# UWB.net
KiCad netlist of a schematic drawn in Altium Designer
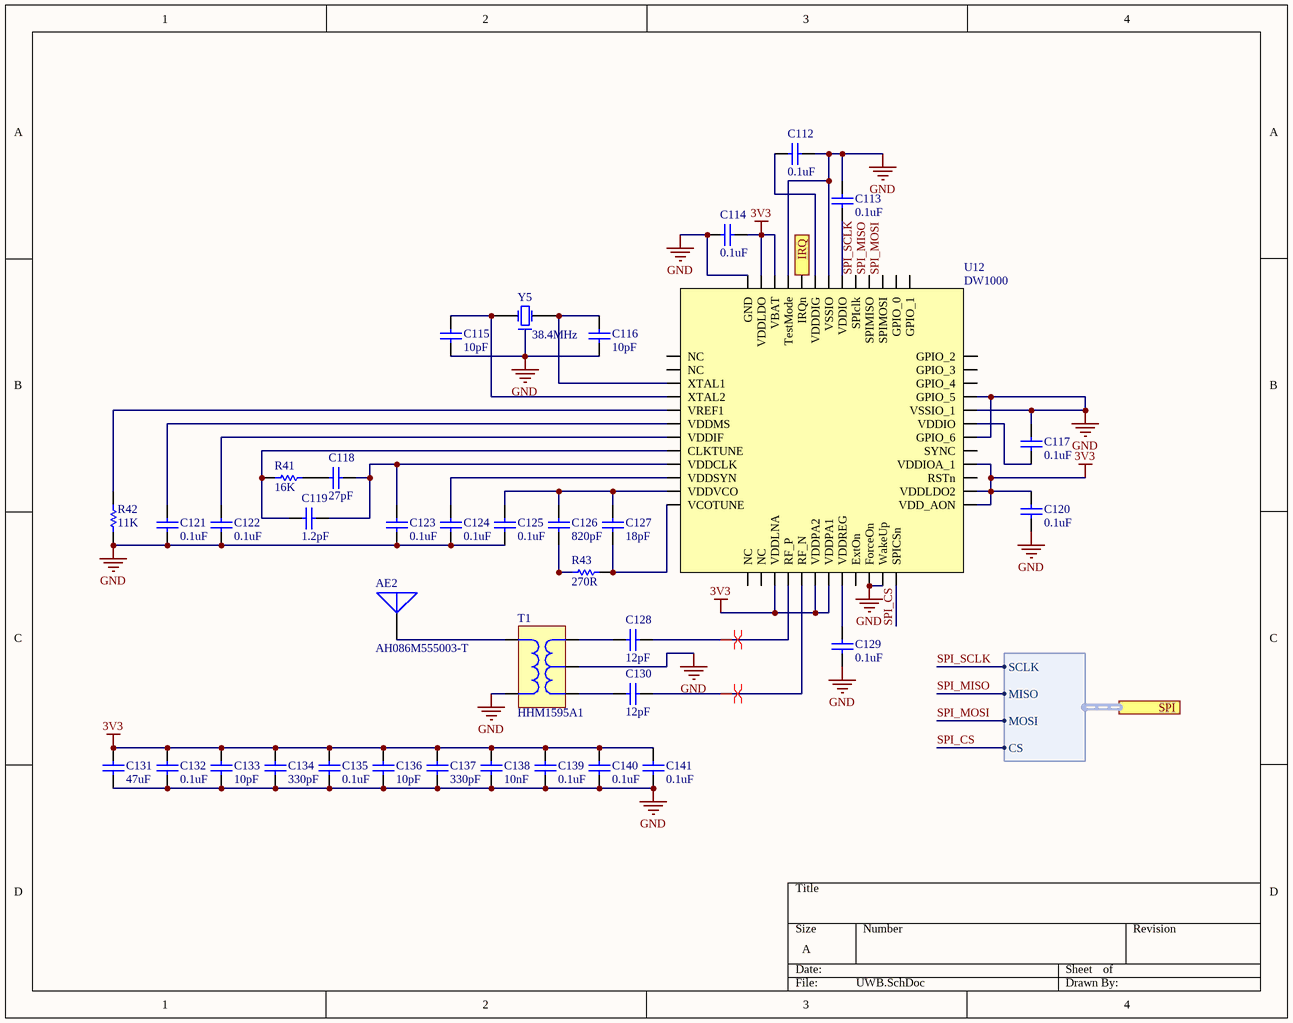
[diagram p0: UWB.SchDoc]

(export (version "E")
  (design (tool "Eeschema 10.0.6"))
  (components
    (comp (ref "AE2")
      (value "AH086M555003-T")
      (footprint "AH086M555003-T")
      (fields (field (name "MANUFACTURER") "Taiyo Yuden"))
      (libsource (lib "Components") (part "AH086M555003-T"))
    )
    (comp (ref "C112")
      (value "0.1uF")
      (footprint "C0402[1005X55]")
      (description "0.1uF 6.3V 10% 0402 (1005 Metric)")
      (fields (field (name "PARTNUMBER") "GRM155R70J104KA01D") (field (name "MANUFACTURER") "Murata"))
      (libsource (lib "Capacitors") (part "CAP_0.1uF_6.3V_0402_10%"))
    )
    (comp (ref "C113")
      (value "0.1uF")
      (footprint "C0402[1005X55]")
      (description "0.1uF 6.3V 10% 0402 (1005 Metric)")
      (fields (field (name "PARTNUMBER") "GRM155R70J104KA01D") (field (name "MANUFACTURER") "Murata"))
      (libsource (lib "Capacitors") (part "CAP_0.1uF_6.3V_0402_10%"))
    )
    (comp (ref "C114")
      (value "0.1uF")
      (footprint "C0402[1005X55]")
      (description "0.1uF 6.3V 10% 0402 (1005 Metric)")
      (fields (field (name "PARTNUMBER") "GRM155R70J104KA01D") (field (name "MANUFACTURER") "Murata"))
      (libsource (lib "Capacitors") (part "CAP_0.1uF_6.3V_0402_10%"))
    )
    (comp (ref "C115")
      (value "10pF")
      (footprint "C0402[1005X55]")
      (description "10pF 50V 1% 0402 (1005 Metric)")
      (fields (field (name "PARTNUMBER") "GRM1555C1H100FA01D") (field (name "MANUFACTURER") "Murata"))
      (libsource (lib "Capacitors") (part "CAP_10pF_50V_0402_1%"))
    )
    (comp (ref "C116")
      (value "10pF")
      (footprint "C0402[1005X55]")
      (description "10pF 50V 1% 0402 (1005 Metric)")
      (fields (field (name "PARTNUMBER") "GRM1555C1H100FA01D") (field (name "MANUFACTURER") "Murata"))
      (libsource (lib "Capacitors") (part "CAP_10pF_50V_0402_1%"))
    )
    (comp (ref "C117")
      (value "0.1uF")
      (footprint "C0402[1005X55]")
      (description "0.1uF 6.3V 10% 0402 (1005 Metric)")
      (fields (field (name "PARTNUMBER") "GRM155R70J104KA01D") (field (name "MANUFACTURER") "Murata"))
      (libsource (lib "Capacitors") (part "CAP_0.1uF_6.3V_0402_10%"))
    )
    (comp (ref "C118")
      (value "27pF")
      (footprint "C0402[1005X55]")
      (description "27pF 50V 1% 0402 (1005 Metric)")
      (fields (field (name "PARTNUMBER") "GRM1555C1H270FA01D") (field (name "MANUFACTURER") "Murata"))
      (libsource (lib "Capacitors") (part "CAP_27pF_50V_0402_1%"))
    )
    (comp (ref "C119")
      (value "1.2pF")
      (footprint "C0402[1005X55]")
      (description "1.2pF 50V 0.05pF 0402 (1005 Metric)")
      (fields (field (name "PARTNUMBER") "GRM1555C1H1R2WA01D") (field (name "MANUFACTURER") "Murata"))
      (libsource (lib "Capacitors") (part "CAP_1.2pF_50V_0402_0.05pF"))
    )
    (comp (ref "C120")
      (value "0.1uF")
      (footprint "C0402[1005X55]")
      (description "0.1uF 6.3V 10% 0402 (1005 Metric)")
      (fields (field (name "PARTNUMBER") "GRM155R70J104KA01D") (field (name "MANUFACTURER") "Murata"))
      (libsource (lib "Capacitors") (part "CAP_0.1uF_6.3V_0402_10%"))
    )
    (comp (ref "C121")
      (value "0.1uF")
      (footprint "C0402[1005X55]")
      (description "0.1uF 6.3V 10% 0402 (1005 Metric)")
      (fields (field (name "PARTNUMBER") "GRM155R70J104KA01D") (field (name "MANUFACTURER") "Murata"))
      (libsource (lib "Capacitors") (part "CAP_0.1uF_6.3V_0402_10%"))
    )
    (comp (ref "C122")
      (value "0.1uF")
      (footprint "C0402[1005X55]")
      (description "0.1uF 6.3V 10% 0402 (1005 Metric)")
      (fields (field (name "PARTNUMBER") "GRM155R70J104KA01D") (field (name "MANUFACTURER") "Murata"))
      (libsource (lib "Capacitors") (part "CAP_0.1uF_6.3V_0402_10%"))
    )
    (comp (ref "C123")
      (value "0.1uF")
      (footprint "C0402[1005X55]")
      (description "0.1uF 6.3V 10% 0402 (1005 Metric)")
      (fields (field (name "PARTNUMBER") "GRM155R70J104KA01D") (field (name "MANUFACTURER") "Murata"))
      (libsource (lib "Capacitors") (part "CAP_0.1uF_6.3V_0402_10%"))
    )
    (comp (ref "C124")
      (value "0.1uF")
      (footprint "C0402[1005X55]")
      (description "0.1uF 6.3V 10% 0402 (1005 Metric)")
      (fields (field (name "PARTNUMBER") "GRM155R70J104KA01D") (field (name "MANUFACTURER") "Murata"))
      (libsource (lib "Capacitors") (part "CAP_0.1uF_6.3V_0402_10%"))
    )
    (comp (ref "C125")
      (value "0.1uF")
      (footprint "C0402[1005X55]")
      (description "0.1uF 6.3V 10% 0402 (1005 Metric)")
      (fields (field (name "PARTNUMBER") "GRM155R70J104KA01D") (field (name "MANUFACTURER") "Murata"))
      (libsource (lib "Capacitors") (part "CAP_0.1uF_6.3V_0402_10%"))
    )
    (comp (ref "C126")
      (value "820pF")
      (footprint "C0402[1005X55]")
      (description "820pF 50V 5% 0402 (1005 Metric)")
      (fields (field (name "PARTNUMBER") "GRM1555C1H821JA01D") (field (name "MANUFACTURER") "Murata"))
      (libsource (lib "Capacitors") (part "CAP_820pF_50V_0402_5%"))
    )
    (comp (ref "C127")
      (value "18pF")
      (footprint "C0402[1005X55]")
      (description "18pF 50V 1% 0402 (1005 Metric)")
      (fields (field (name "PARTNUMBER") "GRM1555C1H180FA01D") (field (name "MANUFACTURER") "Murata"))
      (libsource (lib "Capacitors") (part "CAP_18pF_50V_0402_1%"))
    )
    (comp (ref "C128")
      (value "12pF")
      (footprint "C0402[1005X55]")
      (description "12pF 50V 5% 0402 (1005 Metric)")
      (fields (field (name "PARTNUMBER") "GRM1555C1H120JA01D") (field (name "MANUFACTURER") "Murata"))
      (libsource (lib "Capacitors") (part "CAP_12pF_50V_0402_5%"))
    )
    (comp (ref "C129")
      (value "0.1uF")
      (footprint "C0402[1005X55]")
      (description "0.1uF 6.3V 10% 0402 (1005 Metric)")
      (fields (field (name "PARTNUMBER") "GRM155R70J104KA01D") (field (name "MANUFACTURER") "Murata"))
      (libsource (lib "Capacitors") (part "CAP_0.1uF_6.3V_0402_10%"))
    )
    (comp (ref "C130")
      (value "12pF")
      (footprint "C0402[1005X55]")
      (description "12pF 50V 5% 0402 (1005 Metric)")
      (fields (field (name "PARTNUMBER") "GRM1555C1H120JA01D") (field (name "MANUFACTURER") "Murata"))
      (libsource (lib "Capacitors") (part "CAP_12pF_50V_0402_5%"))
    )
    (comp (ref "C131")
      (value "47uF")
      (footprint "C1206[3216X160]")
      (description "47uF 6.3V 10% 1206 (3216 Metric)")
      (fields (field (name "PARTNUMBER") "GRM31CR60J476KE19L") (field (name "MANUFACTURER") "Murata"))
      (libsource (lib "Capacitors") (part "CAP_47uF_6.3V_1206_10%"))
    )
    (comp (ref "C132")
      (value "0.1uF")
      (footprint "C0402[1005X55]")
      (description "0.1uF 6.3V 10% 0402 (1005 Metric)")
      (fields (field (name "PARTNUMBER") "GRM155R70J104KA01D") (field (name "MANUFACTURER") "Murata"))
      (libsource (lib "Capacitors") (part "CAP_0.1uF_6.3V_0402_10%"))
    )
    (comp (ref "C133")
      (value "10pF")
      (footprint "C0402[1005X55]")
      (description "10pF 50V 1% 0402 (1005 Metric)")
      (fields (field (name "PARTNUMBER") "GRM1555C1H100FA01D") (field (name "MANUFACTURER") "Murata"))
      (libsource (lib "Capacitors") (part "CAP_10pF_50V_0402_1%"))
    )
    (comp (ref "C134")
      (value "330pF")
      (footprint "C0402[1005X55]")
      (description "330pF 50V 5% 0402 (1005 Metric)")
      (fields (field (name "PARTNUMBER") "GRM1555C1H331JA01D") (field (name "MANUFACTURER") "Murata"))
      (libsource (lib "Capacitors") (part "CAP_330pF_50V_0402_5%"))
    )
    (comp (ref "C135")
      (value "0.1uF")
      (footprint "C0402[1005X55]")
      (description "0.1uF 6.3V 10% 0402 (1005 Metric)")
      (fields (field (name "PARTNUMBER") "GRM155R70J104KA01D") (field (name "MANUFACTURER") "Murata"))
      (libsource (lib "Capacitors") (part "CAP_0.1uF_6.3V_0402_10%"))
    )
    (comp (ref "C136")
      (value "10pF")
      (footprint "C0402[1005X55]")
      (description "10pF 50V 1% 0402 (1005 Metric)")
      (fields (field (name "PARTNUMBER") "GRM1555C1H100FA01D") (field (name "MANUFACTURER") "Murata"))
      (libsource (lib "Capacitors") (part "CAP_10pF_50V_0402_1%"))
    )
    (comp (ref "C137")
      (value "330pF")
      (footprint "C0402[1005X55]")
      (description "330pF 50V 5% 0402 (1005 Metric)")
      (fields (field (name "PARTNUMBER") "GRM1555C1H331JA01D") (field (name "MANUFACTURER") "Murata"))
      (libsource (lib "Capacitors") (part "CAP_330pF_50V_0402_5%"))
    )
    (comp (ref "C138")
      (value "10nF")
      (footprint "C0402[1005X55]")
      (description "10nF 50V 10% 0402 (1005 Metric)")
      (fields (field (name "PARTNUMBER") "GCM155R71H103KA55D") (field (name "MANUFACTURER") "Murata"))
      (libsource (lib "Capacitors") (part "CAP_10nF_50V_0402_10%"))
    )
    (comp (ref "C139")
      (value "0.1uF")
      (footprint "C0402[1005X55]")
      (description "0.1uF 6.3V 10% 0402 (1005 Metric)")
      (fields (field (name "PARTNUMBER") "GRM155R70J104KA01D") (field (name "MANUFACTURER") "Murata"))
      (libsource (lib "Capacitors") (part "CAP_0.1uF_6.3V_0402_10%"))
    )
    (comp (ref "C140")
      (value "0.1uF")
      (footprint "C0402[1005X55]")
      (description "0.1uF 6.3V 10% 0402 (1005 Metric)")
      (fields (field (name "PARTNUMBER") "GRM155R70J104KA01D") (field (name "MANUFACTURER") "Murata"))
      (libsource (lib "Capacitors") (part "CAP_0.1uF_6.3V_0402_10%"))
    )
    (comp (ref "C141")
      (value "0.1uF")
      (footprint "C0402[1005X55]")
      (description "0.1uF 6.3V 10% 0402 (1005 Metric)")
      (fields (field (name "PARTNUMBER") "GRM155R70J104KA01D") (field (name "MANUFACTURER") "Murata"))
      (libsource (lib "Capacitors") (part "CAP_0.1uF_6.3V_0402_10%"))
    )
    (comp (ref "R41")
      (value "16K")
      (footprint "R0402[1005]")
      (description "16K 0.063W 1% 0402 (1005 Metric)")
      (fields (field (name "MANUFACTURER") "KOA Speer") (field (name "PARTNUMBER") "RK73H1ETTP1602F"))
      (libsource (lib "Resistors") (part "RES_16K_0402_1%"))
    )
    (comp (ref "R42")
      (value "11K")
      (footprint "R0402[1005]")
      (description "11K 0.063W 1% 0402 (1005 Metric)")
      (fields (field (name "MANUFACTURER") "KOA Speer") (field (name "PARTNUMBER") "RK73H1ETTP1102F"))
      (libsource (lib "Resistors") (part "RES_11K_0402_1%"))
    )
    (comp (ref "R43")
      (value "270R")
      (footprint "R0402[1005]")
      (description "270R 0.063W 1% 0402 (1005 Metric)")
      (fields (field (name "MANUFACTURER") "KOA Speer") (field (name "PARTNUMBER") "RK73H1ETTP2700F"))
      (libsource (lib "Resistors") (part "RES_270R_0402_1%"))
    )
    (comp (ref "T1")
      (value "HHM1595A1")
      (footprint "HHM1595A1")
      (fields (field (name "MANUFACTURER") "TDK"))
      (libsource (lib "Components") (part "HHM1595A1"))
    )
    (comp (ref "U12")
      (value "DW1000")
      (footprint "QFN-48")
      (description "UWB DW1000")
      (fields (field (name "PARTNUMBER") "DW1000-I-TR13") (field (name "MANUFACTURER") "Decawave Limited"))
      (libsource (lib "ICs") (part "DW1000"))
    )
    (comp (ref "Y5")
      (value "38.4MHz")
      (footprint "ABRA-ABM10")
      (fields (field (name "PARTNUMBER") "ABM10-165-38.400MHZ-T3") (field (name "MANUFACTURER") "ABRACON"))
      (libsource (lib "Components") (part "ABM10-165-38.400MHZ-T3"))
    )
  )
  (nets
    (net (code "2") (name "/IRQ") (class "Default")
      (node (ref "U12") (pin "45") (pinfunction "IRQn_45") (pintype "passive"))
    )
    (net (code "3") (name "/SPI_CS") (class "Default")
      (node (ref "U12") (pin "24") (pinfunction "SPICSn_24") (pintype "passive"))
    )
    (net (code "4") (name "/SPI_MISO") (class "Default")
      (node (ref "U12") (pin "40") (pinfunction "SPIMISO_40") (pintype "passive"))
    )
    (net (code "5") (name "/SPI_MOSI") (class "Default")
      (node (ref "U12") (pin "39") (pinfunction "SPIMOSI_39") (pintype "passive"))
    )
    (net (code "6") (name "/SPI_SCLK") (class "Default")
      (node (ref "U12") (pin "41") (pinfunction "SPIclk_41") (pintype "passive"))
    )
    (net (code "8") (name "3V3") (class "Default")
      (node (ref "C114") (pin "1") (pinfunction "1_1") (pintype "passive"))
      (node (ref "C120") (pin "2") (pinfunction "2_2") (pintype "passive"))
      (node (ref "C131") (pin "2") (pinfunction "2_2") (pintype "passive"))
      (node (ref "C132") (pin "2") (pinfunction "2_2") (pintype "passive"))
      (node (ref "C133") (pin "2") (pinfunction "2_2") (pintype "passive"))
      (node (ref "C134") (pin "2") (pinfunction "2_2") (pintype "passive"))
      (node (ref "C135") (pin "2") (pinfunction "2_2") (pintype "passive"))
      (node (ref "C136") (pin "2") (pinfunction "2_2") (pintype "passive"))
      (node (ref "C137") (pin "2") (pinfunction "2_2") (pintype "passive"))
      (node (ref "C138") (pin "2") (pinfunction "2_2") (pintype "passive"))
      (node (ref "C139") (pin "2") (pinfunction "2_2") (pintype "passive"))
      (node (ref "C140") (pin "2") (pinfunction "2_2") (pintype "passive"))
      (node (ref "C141") (pin "2") (pinfunction "2_2") (pintype "passive"))
      (node (ref "U12") (pin "15") (pinfunction "VDDLNA_15") (pintype "passive"))
      (node (ref "U12") (pin "18") (pinfunction "VDDPA2_18") (pintype "passive"))
      (node (ref "U12") (pin "19") (pinfunction "VDDPA1_19") (pintype "passive"))
      (node (ref "U12") (pin "25") (pinfunction "VDD_AON_25") (pintype "passive"))
      (node (ref "U12") (pin "26") (pinfunction "VDDLDO2_26") (pintype "passive"))
      (node (ref "U12") (pin "28") (pinfunction "VDDIOA_1_28") (pintype "passive"))
      (node (ref "U12") (pin "47") (pinfunction "VBAT_47") (pintype "passive"))
      (node (ref "U12") (pin "48") (pinfunction "VDDLDO_48") (pintype "passive"))
    )
    (net (code "9") (name "GND") (class "Default")
      (node (ref "C112") (pin "1") (pinfunction "1_1") (pintype "passive"))
      (node (ref "C113") (pin "2") (pinfunction "2_2") (pintype "passive"))
      (node (ref "C114") (pin "2") (pinfunction "2_2") (pintype "passive"))
      (node (ref "C115") (pin "1") (pinfunction "1_1") (pintype "passive"))
      (node (ref "C116") (pin "1") (pinfunction "1_1") (pintype "passive"))
      (node (ref "C117") (pin "2") (pinfunction "2_2") (pintype "passive"))
      (node (ref "C120") (pin "1") (pinfunction "1_1") (pintype "passive"))
      (node (ref "C121") (pin "1") (pinfunction "1_1") (pintype "passive"))
      (node (ref "C122") (pin "1") (pinfunction "1_1") (pintype "passive"))
      (node (ref "C123") (pin "1") (pinfunction "1_1") (pintype "passive"))
      (node (ref "C124") (pin "1") (pinfunction "1_1") (pintype "passive"))
      (node (ref "C125") (pin "1") (pinfunction "1_1") (pintype "passive"))
      (node (ref "C129") (pin "1") (pinfunction "1_1") (pintype "passive"))
      (node (ref "C131") (pin "1") (pinfunction "1_1") (pintype "passive"))
      (node (ref "C132") (pin "1") (pinfunction "1_1") (pintype "passive"))
      (node (ref "C133") (pin "1") (pinfunction "1_1") (pintype "passive"))
      (node (ref "C134") (pin "1") (pinfunction "1_1") (pintype "passive"))
      (node (ref "C135") (pin "1") (pinfunction "1_1") (pintype "passive"))
      (node (ref "C136") (pin "1") (pinfunction "1_1") (pintype "passive"))
      (node (ref "C137") (pin "1") (pinfunction "1_1") (pintype "passive"))
      (node (ref "C138") (pin "1") (pinfunction "1_1") (pintype "passive"))
      (node (ref "C139") (pin "1") (pinfunction "1_1") (pintype "passive"))
      (node (ref "C140") (pin "1") (pinfunction "1_1") (pintype "passive"))
      (node (ref "C141") (pin "1") (pinfunction "1_1") (pintype "passive"))
      (node (ref "R42") (pin "1") (pinfunction "1_1") (pintype "passive"))
      (node (ref "T1") (pin "2") (pinfunction "2_2") (pintype "passive"))
      (node (ref "T1") (pin "5") (pinfunction "5_5") (pintype "passive"))
      (node (ref "U12") (pin "22") (pinfunction "ForceOn_22") (pintype "passive"))
      (node (ref "U12") (pin "23") (pinfunction "WakeUp_23") (pintype "passive"))
      (node (ref "U12") (pin "30") (pinfunction "GPIO_6_30") (pintype "passive"))
      (node (ref "U12") (pin "32") (pinfunction "VSSIO_1_32") (pintype "passive"))
      (node (ref "U12") (pin "33") (pinfunction "GPIO_5_33") (pintype "passive"))
      (node (ref "U12") (pin "43") (pinfunction "VSSIO_43") (pintype "passive"))
      (node (ref "U12") (pin "46") (pinfunction "TestMode_46") (pintype "passive"))
      (node (ref "U12") (pin "49") (pinfunction "GND_49") (pintype "passive"))
      (node (ref "Y5") (pin "2") (pinfunction "2_2") (pintype "passive"))
    )
    (net (code "10") (name "Net-(AE2-Pad1)") (class "Default")
      (node (ref "AE2") (pin "1") (pinfunction "1_1") (pintype "passive"))
      (node (ref "T1") (pin "1") (pinfunction "1_1") (pintype "passive"))
    )
    (net (code "11") (name "Net-(C113-Pad1)") (class "Default")
      (node (ref "C113") (pin "1") (pinfunction "1_1") (pintype "passive"))
      (node (ref "U12") (pin "42") (pinfunction "VDDIO_42") (pintype "passive"))
    )
    (net (code "12") (name "Net-(C117-Pad1)") (class "Default")
      (node (ref "C117") (pin "1") (pinfunction "1_1") (pintype "passive"))
      (node (ref "U12") (pin "31") (pinfunction "VDDIO_31") (pintype "passive"))
    )
    (net (code "13") (name "Net-(C118-Pad2)") (class "Default")
      (node (ref "C118") (pin "2") (pinfunction "2_2") (pintype "passive"))
      (node (ref "R41") (pin "1") (pinfunction "1_1") (pintype "passive"))
    )
    (net (code "14") (name "Net-(C126-Pad1)") (class "Default")
      (node (ref "C126") (pin "1") (pinfunction "1_1") (pintype "passive"))
      (node (ref "R43") (pin "1") (pinfunction "1_1") (pintype "passive"))
    )
    (net (code "15") (name "Net-(C128-Pad1)") (class "Default")
      (node (ref "C128") (pin "1") (pinfunction "1_1") (pintype "passive"))
      (node (ref "T1") (pin "4") (pinfunction "4_4") (pintype "passive"))
    )
    (net (code "16") (name "Net-(C130-Pad1)") (class "Default")
      (node (ref "C130") (pin "1") (pinfunction "1_1") (pintype "passive"))
      (node (ref "T1") (pin "3") (pinfunction "3_3") (pintype "passive"))
    )
    (net (code "17") (name "Net-(U12-CLKTUNE)") (class "Default")
      (node (ref "C119") (pin "2") (pinfunction "2_2") (pintype "passive"))
      (node (ref "R41") (pin "2") (pinfunction "2_2") (pintype "passive"))
      (node (ref "U12") (pin "8") (pinfunction "CLKTUNE_8") (pintype "passive"))
    )
    (net (code "18") (name "Net-(U12-RF_N)") (class "Default")
      (node (ref "C130") (pin "2") (pinfunction "2_2") (pintype "passive"))
      (node (ref "U12") (pin "17") (pinfunction "RF_N_17") (pintype "passive"))
    )
    (net (code "19") (name "Net-(U12-RF_P)") (class "Default")
      (node (ref "C128") (pin "2") (pinfunction "2_2") (pintype "passive"))
      (node (ref "U12") (pin "16") (pinfunction "RF_P_16") (pintype "passive"))
    )
    (net (code "20") (name "Net-(U12-VCOTUNE)") (class "Default")
      (node (ref "C127") (pin "1") (pinfunction "1_1") (pintype "passive"))
      (node (ref "R43") (pin "2") (pinfunction "2_2") (pintype "passive"))
      (node (ref "U12") (pin "12") (pinfunction "VCOTUNE_12") (pintype "passive"))
    )
    (net (code "21") (name "Net-(U12-VDDCLK)") (class "Default")
      (node (ref "C118") (pin "1") (pinfunction "1_1") (pintype "passive"))
      (node (ref "C119") (pin "1") (pinfunction "1_1") (pintype "passive"))
      (node (ref "C123") (pin "2") (pinfunction "2_2") (pintype "passive"))
      (node (ref "U12") (pin "9") (pinfunction "VDDCLK_9") (pintype "passive"))
    )
    (net (code "22") (name "Net-(U12-VDDDIG)") (class "Default")
      (node (ref "C112") (pin "2") (pinfunction "2_2") (pintype "passive"))
      (node (ref "U12") (pin "44") (pinfunction "VDDDIG_44") (pintype "passive"))
    )
    (net (code "23") (name "Net-(U12-VDDIF)") (class "Default")
      (node (ref "C122") (pin "2") (pinfunction "2_2") (pintype "passive"))
      (node (ref "U12") (pin "7") (pinfunction "VDDIF_7") (pintype "passive"))
    )
    (net (code "24") (name "Net-(U12-VDDMS)") (class "Default")
      (node (ref "C121") (pin "2") (pinfunction "2_2") (pintype "passive"))
      (node (ref "U12") (pin "6") (pinfunction "VDDMS_6") (pintype "passive"))
    )
    (net (code "25") (name "Net-(U12-VDDREG)") (class "Default")
      (node (ref "C129") (pin "2") (pinfunction "2_2") (pintype "passive"))
      (node (ref "U12") (pin "20") (pinfunction "VDDREG_20") (pintype "passive"))
    )
    (net (code "26") (name "Net-(U12-VDDSYN)") (class "Default")
      (node (ref "C124") (pin "2") (pinfunction "2_2") (pintype "passive"))
      (node (ref "U12") (pin "10") (pinfunction "VDDSYN_10") (pintype "passive"))
    )
    (net (code "27") (name "Net-(U12-VDDVCO)") (class "Default")
      (node (ref "C125") (pin "2") (pinfunction "2_2") (pintype "passive"))
      (node (ref "C126") (pin "2") (pinfunction "2_2") (pintype "passive"))
      (node (ref "C127") (pin "2") (pinfunction "2_2") (pintype "passive"))
      (node (ref "U12") (pin "11") (pinfunction "VDDVCO_11") (pintype "passive"))
    )
    (net (code "28") (name "Net-(U12-VREF1)") (class "Default")
      (node (ref "R42") (pin "2") (pinfunction "2_2") (pintype "passive"))
      (node (ref "U12") (pin "5") (pinfunction "VREF1_5") (pintype "passive"))
    )
    (net (code "29") (name "Net-(U12-XTAL1)") (class "Default")
      (node (ref "C116") (pin "2") (pinfunction "2_2") (pintype "passive"))
      (node (ref "U12") (pin "3") (pinfunction "XTAL1_3") (pintype "passive"))
      (node (ref "Y5") (pin "3") (pinfunction "X2_3") (pintype "passive"))
    )
    (net (code "30") (name "Net-(U12-XTAL2)") (class "Default")
      (node (ref "C115") (pin "2") (pinfunction "2_2") (pintype "passive"))
      (node (ref "U12") (pin "4") (pinfunction "XTAL2_4") (pintype "passive"))
      (node (ref "Y5") (pin "1") (pinfunction "X1_1") (pintype "passive"))
    )
    (net (code "31") (name "unconnected-(U12-ExtOn-Pad21)") (class "Default")
      (node (ref "U12") (pin "21") (pinfunction "ExtOn_21") (pintype "passive"))
    )
    (net (code "32") (name "unconnected-(U12-GPIO_0-Pad38)") (class "Default")
      (node (ref "U12") (pin "38") (pinfunction "GPIO_0_38") (pintype "passive"))
    )
    (net (code "33") (name "unconnected-(U12-GPIO_1-Pad37)") (class "Default")
      (node (ref "U12") (pin "37") (pinfunction "GPIO_1_37") (pintype "passive"))
    )
    (net (code "34") (name "unconnected-(U12-GPIO_2-Pad36)") (class "Default")
      (node (ref "U12") (pin "36") (pinfunction "GPIO_2_36") (pintype "passive"))
    )
    (net (code "35") (name "unconnected-(U12-GPIO_3-Pad35)") (class "Default")
      (node (ref "U12") (pin "35") (pinfunction "GPIO_3_35") (pintype "passive"))
    )
    (net (code "36") (name "unconnected-(U12-GPIO_4-Pad34)") (class "Default")
      (node (ref "U12") (pin "34") (pinfunction "GPIO_4_34") (pintype "passive"))
    )
    (net (code "37") (name "unconnected-(U12-NC-Pad1)") (class "Default")
      (node (ref "U12") (pin "1") (pinfunction "NC_1") (pintype "passive"))
    )
    (net (code "38") (name "unconnected-(U12-NC-Pad2)") (class "Default")
      (node (ref "U12") (pin "2") (pinfunction "NC_2") (pintype "passive"))
    )
    (net (code "39") (name "unconnected-(U12-NC-Pad13)") (class "Default")
      (node (ref "U12") (pin "13") (pinfunction "NC_13") (pintype "passive"))
    )
    (net (code "40") (name "unconnected-(U12-NC-Pad14)") (class "Default")
      (node (ref "U12") (pin "14") (pinfunction "NC_14") (pintype "passive"))
    )
    (net (code "41") (name "unconnected-(U12-RSTn-Pad27)") (class "Default")
      (node (ref "U12") (pin "27") (pinfunction "RSTn_27") (pintype "passive"))
    )
    (net (code "42") (name "unconnected-(U12-SYNC-Pad29)") (class "Default")
      (node (ref "U12") (pin "29") (pinfunction "SYNC_29") (pintype "passive"))
    )
  )
)
